# Sheet3.net
KiCad netlist of a schematic drawn in Altium Designer
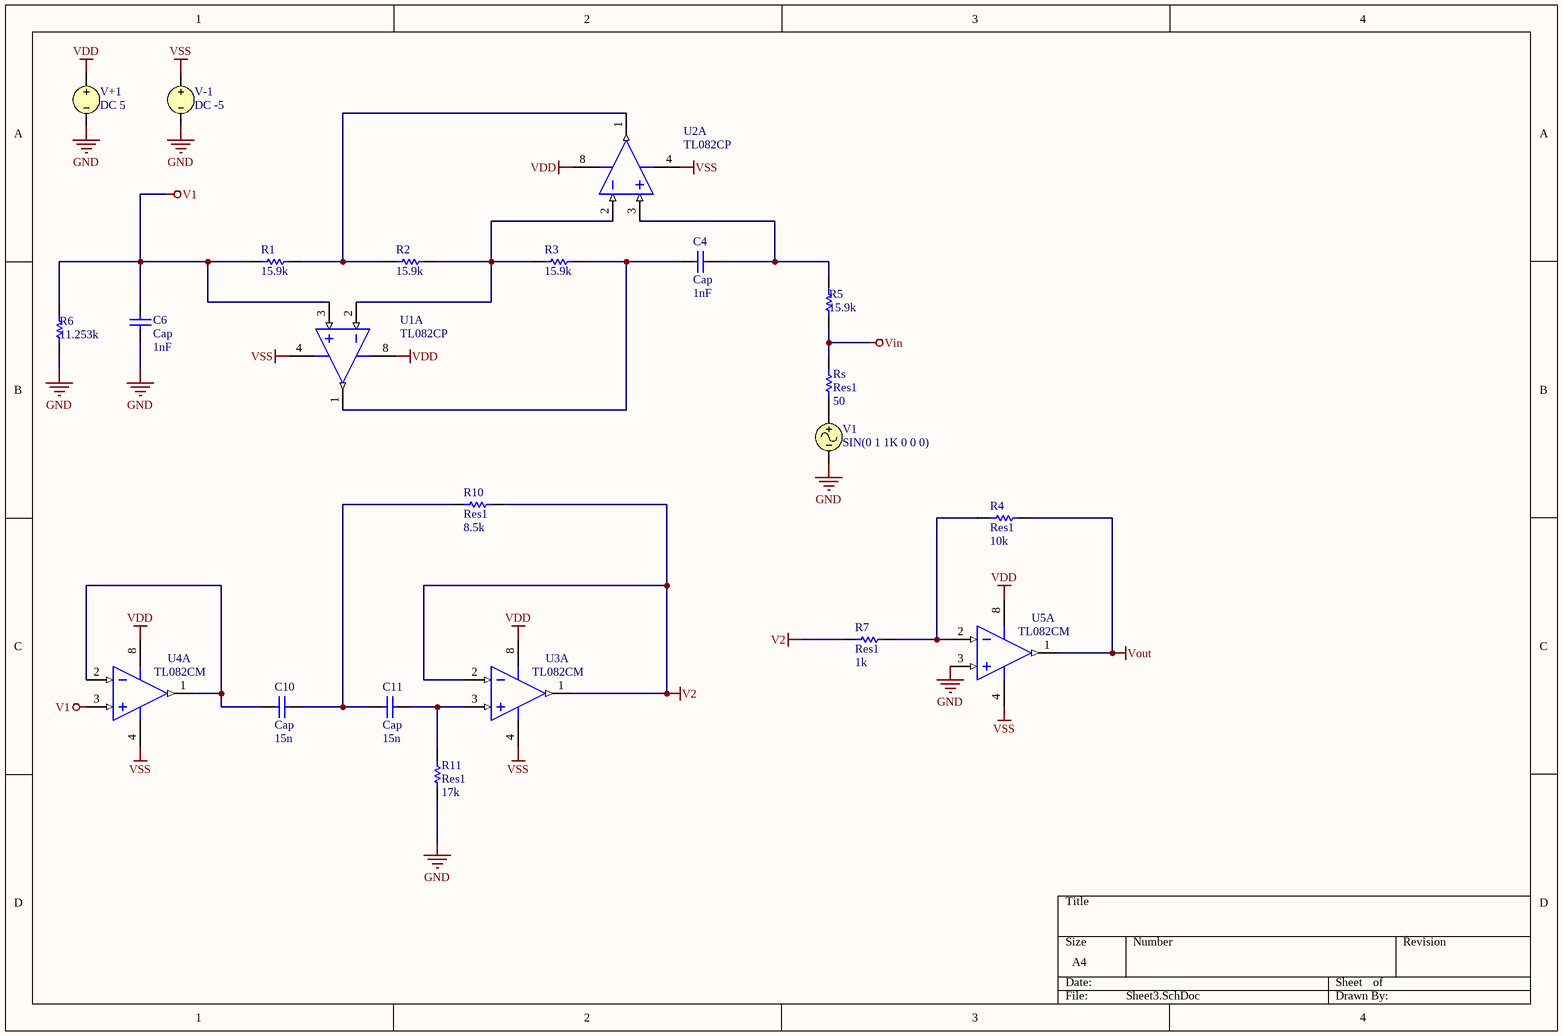
[diagram p0: Sheet3.SchDoc]

(export (version "E")
  (design (tool "Eeschema 10.0.6"))
  (components
    (comp (ref "C4")
      (value "Cap")
      (footprint "RAD-0.3")
      (description "Capacitor")
      (fields (field (name "ALTIUM_VALUE") "1nF") (field (name "PUBLISHER") "Altium Limited"))
      (libsource (lib "Miscellaneous Devices") (part "Cap"))
    )
    (comp (ref "C6")
      (value "Cap")
      (footprint "RAD-0.3")
      (description "Capacitor")
      (fields (field (name "ALTIUM_VALUE") "1nF") (field (name "PUBLISHER") "Altium Limited"))
      (libsource (lib "Miscellaneous Devices") (part "Cap"))
    )
    (comp (ref "C10")
      (value "Cap")
      (footprint "RAD-0.3")
      (description "Capacitor")
      (fields (field (name "ALTIUM_VALUE") "15n") (field (name "PUBLISHER") "Altium Limited"))
      (libsource (lib "Miscellaneous Devices") (part "Cap"))
    )
    (comp (ref "C11")
      (value "Cap")
      (footprint "RAD-0.3")
      (description "Capacitor")
      (fields (field (name "ALTIUM_VALUE") "15n") (field (name "PUBLISHER") "Altium Limited"))
      (libsource (lib "Miscellaneous Devices") (part "Cap"))
    )
    (comp (ref "R1")
      (value "15.9k")
      (footprint "AXIAL-0.3")
      (description "Resistor")
      (fields (field (name "Comment") "Res1") (field (name "PUBLISHER") "Altium Limited"))
      (libsource (lib "Miscellaneous Devices") (part "Res1"))
    )
    (comp (ref "R2")
      (value "15.9k")
      (footprint "AXIAL-0.3")
      (description "Resistor")
      (fields (field (name "Comment") "Res1") (field (name "PUBLISHER") "Altium Limited"))
      (libsource (lib "Miscellaneous Devices") (part "Res1"))
    )
    (comp (ref "R3")
      (value "15.9k")
      (footprint "AXIAL-0.3")
      (description "Resistor")
      (fields (field (name "Comment") "Res1") (field (name "PUBLISHER") "Altium Limited"))
      (libsource (lib "Miscellaneous Devices") (part "Res1"))
    )
    (comp (ref "R4")
      (value "Res1")
      (footprint "AXIAL-0.3")
      (description "Resistor")
      (fields (field (name "ALTIUM_VALUE") "10k") (field (name "PUBLISHER") "Altium Limited"))
      (libsource (lib "Miscellaneous Devices") (part "Res1"))
    )
    (comp (ref "R5")
      (value "15.9k")
      (footprint "AXIAL-0.3")
      (description "Resistor")
      (fields (field (name "Comment") "Res1") (field (name "PUBLISHER") "Altium Limited"))
      (libsource (lib "Miscellaneous Devices") (part "Res1"))
    )
    (comp (ref "R6")
      (value "11.253k")
      (footprint "AXIAL-0.3")
      (description "Resistor")
      (fields (field (name "Comment") "Res1") (field (name "PUBLISHER") "Altium Limited"))
      (libsource (lib "Miscellaneous Devices") (part "Res1"))
    )
    (comp (ref "R7")
      (value "Res1")
      (footprint "AXIAL-0.3")
      (description "Resistor")
      (fields (field (name "ALTIUM_VALUE") "1k") (field (name "PUBLISHER") "Altium Limited"))
      (libsource (lib "Miscellaneous Devices") (part "Res1"))
    )
    (comp (ref "R10")
      (value "Res1")
      (footprint "AXIAL-0.3")
      (description "Resistor")
      (fields (field (name "ALTIUM_VALUE") "8.5k") (field (name "PUBLISHER") "Altium Limited"))
      (libsource (lib "Miscellaneous Devices") (part "Res1"))
    )
    (comp (ref "R11")
      (value "Res1")
      (footprint "AXIAL-0.3")
      (description "Resistor")
      (fields (field (name "ALTIUM_VALUE") "17k") (field (name "PUBLISHER") "Altium Limited"))
      (libsource (lib "Miscellaneous Devices") (part "Res1"))
    )
    (comp (ref "Rs")
      (value "Res1")
      (footprint "AXIAL-0.3")
      (description "Resistor")
      (fields (field (name "ALTIUM_VALUE") "50") (field (name "PUBLISHER") "Altium Limited"))
      (libsource (lib "Miscellaneous Devices") (part "Res1"))
    )
    (comp (ref "U1")
      (value "TL082CP")
      (footprint "N08E")
      (description "Wide Bandwidth Dual JFET Input Operational Amplifier")
      (fields
        (field (name "MANUFACTURER") "National Semiconductor")
        (field (name "PUBLISHER") "Altium Limited")
      )
      (libsource (lib "NSC Amplifier") (part "TL082CP"))
    )
    (comp (ref "U2")
      (value "TL082CP")
      (footprint "N08E")
      (description "Wide Bandwidth Dual JFET Input Operational Amplifier")
      (fields
        (field (name "MANUFACTURER") "National Semiconductor")
        (field (name "PUBLISHER") "Altium Limited")
      )
      (libsource (lib "NSC Amplifier") (part "TL082CP"))
    )
    (comp (ref "U3")
      (value "TL082CM")
      (footprint "M08A_N")
      (description "Wide Bandwidth Dual JFET Input Operational Amplifier")
      (fields
        (field (name "MANUFACTURER") "National Semiconductor")
        (field (name "DIGIKEYPARTNUMBER") "TL082CM-ND")
        (field (name "PUBLISHER") "Altium Limited")
      )
      (libsource (lib "NSC Amplifier") (part "TL082CM"))
    )
    (comp (ref "U4")
      (value "TL082CM")
      (footprint "M08A_N")
      (description "Wide Bandwidth Dual JFET Input Operational Amplifier")
      (fields
        (field (name "MANUFACTURER") "National Semiconductor")
        (field (name "DIGIKEYPARTNUMBER") "TL082CM-ND")
        (field (name "PUBLISHER") "Altium Limited")
      )
      (libsource (lib "NSC Amplifier") (part "TL082CM"))
    )
    (comp (ref "U5")
      (value "TL082CM")
      (footprint "M08A_N")
      (description "Wide Bandwidth Dual JFET Input Operational Amplifier")
      (fields
        (field (name "MANUFACTURER") "National Semiconductor")
        (field (name "DIGIKEYPARTNUMBER") "TL082CM-ND")
        (field (name "PUBLISHER") "Altium Limited")
      )
      (libsource (lib "NSC Amplifier") (part "TL082CM"))
    )
    (comp (ref "V+1")
      (value "DC 5")
      (description "Voltage Source")
      (fields (field (name "PUBLISHER") "Altium Limited"))
      (libsource (lib "Simulation Sources") (part "VSRC"))
    )
    (comp (ref "V-1")
      (value "DC -5")
      (description "Voltage Source")
      (fields (field (name "PUBLISHER") "Altium Limited"))
      (libsource (lib "Simulation Sources") (part "VSRC"))
    )
    (comp (ref "V1")
      (value "SIN(0 1 1K 0 0 0)")
      (description "Sinusoidal Voltage Source")
      (fields (field (name "PUBLISHER") "Altium Limited"))
      (libsource (lib "Simulation Sources") (part "VSIN"))
    )
  )
  (nets
    (net (code "1") (name "GND") (class "Default")
      (node (ref "C6") (pin "2") (pinfunction "2_2") (pintype "passive"))
      (node (ref "R11") (pin "1") (pinfunction "1_1") (pintype "passive"))
      (node (ref "R6") (pin "1") (pinfunction "1_1") (pintype "passive"))
      (node (ref "U5") (pin "3") (pinfunction "INA+_3") (pintype "input"))
      (node (ref "V+1") (pin "2") (pinfunction "2_2") (pintype "passive"))
      (node (ref "V-1") (pin "2") (pinfunction "2_2") (pintype "passive"))
      (node (ref "V1") (pin "2") (pinfunction "2_2") (pintype "passive"))
    )
    (net (code "2") (name "Net-(C10-Pad2)") (class "Default")
      (node (ref "C10") (pin "2") (pinfunction "2_2") (pintype "passive"))
      (node (ref "C11") (pin "1") (pinfunction "1_1") (pintype "passive"))
      (node (ref "R10") (pin "1") (pinfunction "1_1") (pintype "passive"))
    )
    (net (code "3") (name "Net-(Rs-Pad1)") (class "Default")
      (node (ref "Rs") (pin "1") (pinfunction "1_1") (pintype "passive"))
      (node (ref "V1") (pin "1") (pinfunction "1_1") (pintype "passive"))
    )
    (net (code "4") (name "Net-(U1A-INA-)") (class "Default")
      (node (ref "R2") (pin "1") (pinfunction "1_1") (pintype "passive"))
      (node (ref "R3") (pin "2") (pinfunction "2_2") (pintype "passive"))
      (node (ref "U1") (pin "2") (pinfunction "INA-_2") (pintype "input"))
      (node (ref "U2") (pin "2") (pinfunction "INA-_2") (pintype "input"))
    )
    (net (code "5") (name "Net-(U1A-OUTA)") (class "Default")
      (node (ref "C4") (pin "1") (pinfunction "1_1") (pintype "passive"))
      (node (ref "R3") (pin "1") (pinfunction "1_1") (pintype "passive"))
      (node (ref "U1") (pin "1") (pinfunction "OUTA_1") (pintype "output"))
    )
    (net (code "6") (name "Net-(U2A-INA+)") (class "Default")
      (node (ref "C4") (pin "2") (pinfunction "2_2") (pintype "passive"))
      (node (ref "R5") (pin "2") (pinfunction "2_2") (pintype "passive"))
      (node (ref "U2") (pin "3") (pinfunction "INA+_3") (pintype "input"))
    )
    (net (code "7") (name "Net-(U2A-OUTA)") (class "Default")
      (node (ref "R1") (pin "1") (pinfunction "1_1") (pintype "passive"))
      (node (ref "R2") (pin "2") (pinfunction "2_2") (pintype "passive"))
      (node (ref "U2") (pin "1") (pinfunction "OUTA_1") (pintype "output"))
    )
    (net (code "8") (name "Net-(U3A-INA+)") (class "Default")
      (node (ref "C11") (pin "2") (pinfunction "2_2") (pintype "passive"))
      (node (ref "R11") (pin "2") (pinfunction "2_2") (pintype "passive"))
      (node (ref "U3") (pin "3") (pinfunction "INA+_3") (pintype "input"))
    )
    (net (code "9") (name "Net-(U4A-INA-)") (class "Default")
      (node (ref "C10") (pin "1") (pinfunction "1_1") (pintype "passive"))
      (node (ref "U4") (pin "1") (pinfunction "OUTA_1") (pintype "output"))
      (node (ref "U4") (pin "2") (pinfunction "INA-_2") (pintype "input"))
    )
    (net (code "10") (name "Net-(U5A-INA-)") (class "Default")
      (node (ref "R4") (pin "1") (pinfunction "1_1") (pintype "passive"))
      (node (ref "R7") (pin "2") (pinfunction "2_2") (pintype "passive"))
      (node (ref "U5") (pin "2") (pinfunction "INA-_2") (pintype "input"))
    )
    (net (code "11") (name "V1") (class "Default")
      (node (ref "C6") (pin "1") (pinfunction "1_1") (pintype "passive"))
      (node (ref "R1") (pin "2") (pinfunction "2_2") (pintype "passive"))
      (node (ref "R6") (pin "2") (pinfunction "2_2") (pintype "passive"))
      (node (ref "U1") (pin "3") (pinfunction "INA+_3") (pintype "input"))
      (node (ref "U4") (pin "3") (pinfunction "INA+_3") (pintype "input"))
    )
    (net (code "12") (name "V2") (class "Default")
      (node (ref "R10") (pin "2") (pinfunction "2_2") (pintype "passive"))
      (node (ref "R7") (pin "1") (pinfunction "1_1") (pintype "passive"))
      (node (ref "U3") (pin "1") (pinfunction "OUTA_1") (pintype "output"))
      (node (ref "U3") (pin "2") (pinfunction "INA-_2") (pintype "input"))
    )
    (net (code "13") (name "VDD") (class "Default")
      (node (ref "U1") (pin "8") (pinfunction "V+_8") (pintype "power_in"))
      (node (ref "U2") (pin "8") (pinfunction "V+_8") (pintype "power_in"))
      (node (ref "U3") (pin "8") (pinfunction "V+_8") (pintype "power_in"))
      (node (ref "U4") (pin "8") (pinfunction "V+_8") (pintype "power_in"))
      (node (ref "U5") (pin "8") (pinfunction "V+_8") (pintype "power_in"))
      (node (ref "V+1") (pin "1") (pinfunction "1_1") (pintype "passive"))
    )
    (net (code "14") (name "VSS") (class "Default")
      (node (ref "U1") (pin "4") (pinfunction "V-_4") (pintype "power_in"))
      (node (ref "U2") (pin "4") (pinfunction "V-_4") (pintype "power_in"))
      (node (ref "U3") (pin "4") (pinfunction "V-_4") (pintype "power_in"))
      (node (ref "U4") (pin "4") (pinfunction "V-_4") (pintype "power_in"))
      (node (ref "U5") (pin "4") (pinfunction "V-_4") (pintype "power_in"))
      (node (ref "V-1") (pin "1") (pinfunction "1_1") (pintype "passive"))
    )
    (net (code "15") (name "Vin") (class "Default")
      (node (ref "R5") (pin "1") (pinfunction "1_1") (pintype "passive"))
      (node (ref "Rs") (pin "2") (pinfunction "2_2") (pintype "passive"))
    )
    (net (code "16") (name "Vout") (class "Default")
      (node (ref "R4") (pin "2") (pinfunction "2_2") (pintype "passive"))
      (node (ref "U5") (pin "1") (pinfunction "OUTA_1") (pintype "output"))
    )
  )
)
